# TSAL_inverter_voltage_measurement_TNN_V1.net
KiCad netlist of a schematic drawn in EAGLE
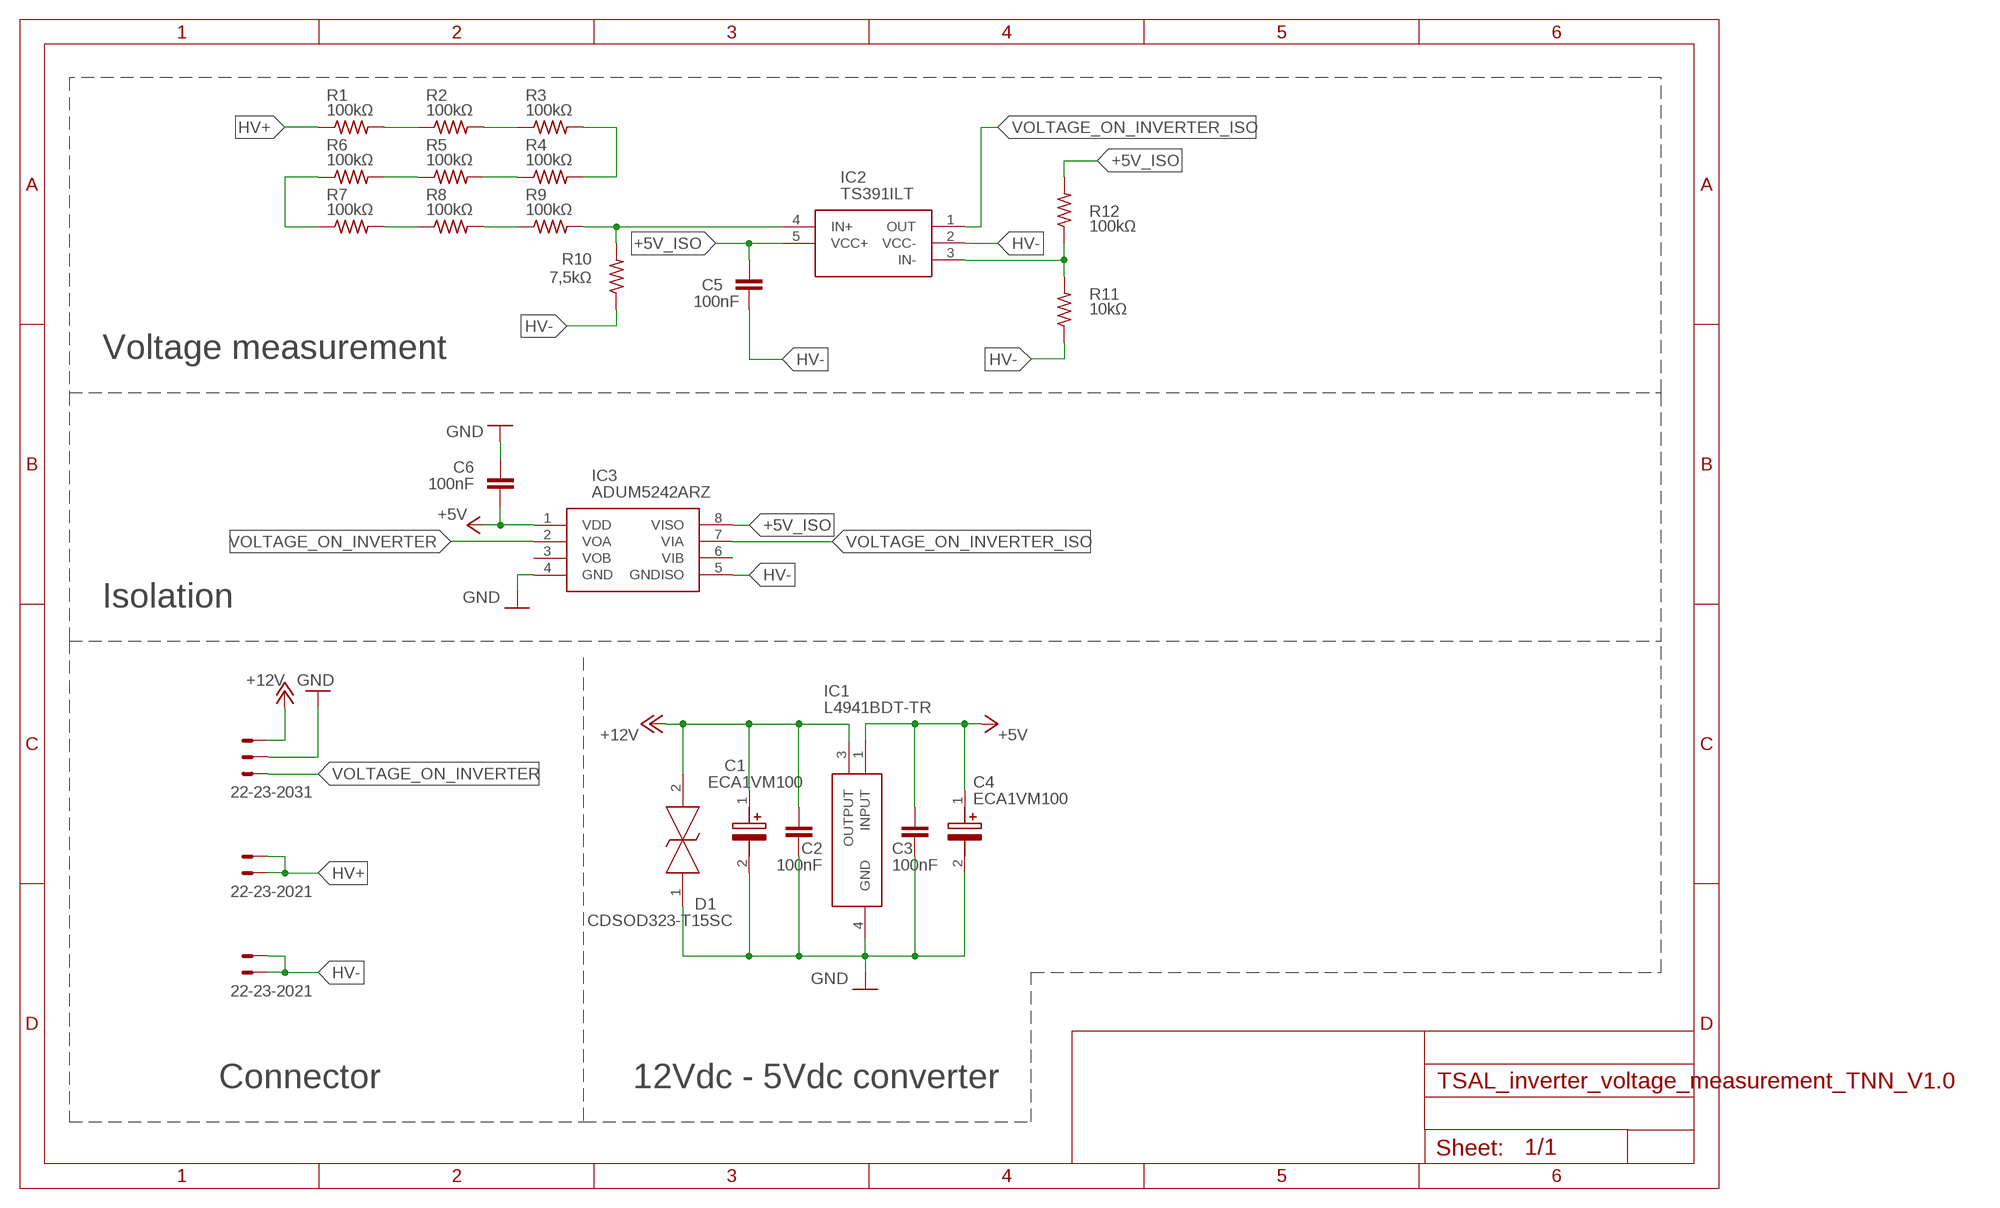
[diagram p0: schematic, sheet 1]

(export (version "E")
  (design (tool "Eeschema 10.0.6"))
  (components
    (comp (ref "C1")
      (value "ECA1VM100")
      (footprint "eagle-import:CAPPRD200W55D525H1200")
      (libsource (lib "eagle-import") (part "ECA1VM100"))
    )
    (comp (ref "C2")
      (value "100nF")
      (footprint "eagle-import:C0603")
      (libsource (lib "eagle-import") (part "C-EUC0603"))
    )
    (comp (ref "C3")
      (value "100nF")
      (footprint "eagle-import:C0603")
      (libsource (lib "eagle-import") (part "C-EUC0603"))
    )
    (comp (ref "C4")
      (value "ECA1VM100")
      (footprint "eagle-import:CAPPRD200W55D525H1200")
      (libsource (lib "eagle-import") (part "ECA1VM100"))
    )
    (comp (ref "C5")
      (value "100nF")
      (footprint "eagle-import:C0603")
      (libsource (lib "eagle-import") (part "C-EUC0603"))
    )
    (comp (ref "C6")
      (value "100nF")
      (footprint "eagle-import:C0603")
      (libsource (lib "eagle-import") (part "C-EUC0603"))
    )
    (comp (ref "D1")
      (value "CDSOD323-T15SC")
      (footprint "eagle-import:SOD-323")
      (fields (field (name "MOUSER_PART_NUMBER") "652-CDSOD323-T15SC"))
      (libsource (lib "eagle-import") (part "CDSOD323-T15SC"))
    )
    (comp (ref "HV+")
      (value "22-23-2021")
      (footprint "eagle-import:22-23-2021")
      (fields (field (name "MF") "MOLEX"))
      (libsource (lib "eagle-import") (part "22-23-2021"))
    )
    (comp (ref "HV-")
      (value "22-23-2021")
      (footprint "eagle-import:22-23-2021")
      (fields (field (name "MF") "MOLEX"))
      (libsource (lib "eagle-import") (part "22-23-2021"))
    )
    (comp (ref "IC1")
      (value "L4941BDT-TR")
      (footprint "eagle-import:TO228P972X240-3N")
      (fields (field (name "MOUSER_PART_NUMBER") "511-L4941BDT-TR"))
      (libsource (lib "eagle-import") (part "L4941BDT-TR"))
    )
    (comp (ref "IC2")
      (value "TS391ILT")
      (footprint "eagle-import:SOT95P280X145-5N")
      (fields (field (name "MOUSER_PART_NUMBER") "511-TS391IL"))
      (libsource (lib "eagle-import") (part "TS391ILT"))
    )
    (comp (ref "IC3")
      (value "ADUM5242ARZ")
      (footprint "eagle-import:SOIC127P600X175-8N")
      (fields (field (name "MOUSER_PART_NUMBER") "584-ADUM5242ARZ"))
      (libsource (lib "eagle-import") (part "ADUM5242ARZ"))
    )
    (comp (ref "LOW_VOLTAGE")
      (value "22-23-2031")
      (footprint "eagle-import:22-23-2031")
      (fields (field (name "MF") "MOLEX"))
      (libsource (lib "eagle-import") (part "22-23-2031"))
    )
    (comp (ref "R1")
      (value "100kΩ")
      (footprint "eagle-import:R0603")
      (libsource (lib "eagle-import") (part "R-US_R0603"))
    )
    (comp (ref "R2")
      (value "100kΩ")
      (footprint "eagle-import:R0603")
      (libsource (lib "eagle-import") (part "R-US_R0603"))
    )
    (comp (ref "R3")
      (value "100kΩ")
      (footprint "eagle-import:R0603")
      (libsource (lib "eagle-import") (part "R-US_R0603"))
    )
    (comp (ref "R4")
      (value "100kΩ")
      (footprint "eagle-import:R0603")
      (libsource (lib "eagle-import") (part "R-US_R0603"))
    )
    (comp (ref "R5")
      (value "100kΩ")
      (footprint "eagle-import:R0603")
      (libsource (lib "eagle-import") (part "R-US_R0603"))
    )
    (comp (ref "R6")
      (value "100kΩ")
      (footprint "eagle-import:R0603")
      (libsource (lib "eagle-import") (part "R-US_R0603"))
    )
    (comp (ref "R7")
      (value "100kΩ")
      (footprint "eagle-import:R0603")
      (libsource (lib "eagle-import") (part "R-US_R0603"))
    )
    (comp (ref "R8")
      (value "100kΩ")
      (footprint "eagle-import:R0603")
      (libsource (lib "eagle-import") (part "R-US_R0603"))
    )
    (comp (ref "R9")
      (value "100kΩ")
      (footprint "eagle-import:R0603")
      (libsource (lib "eagle-import") (part "R-US_R0603"))
    )
    (comp (ref "R10")
      (value "7,5kΩ")
      (footprint "eagle-import:R0603")
      (libsource (lib "eagle-import") (part "R-US_R0603"))
    )
    (comp (ref "R11")
      (value "10kΩ")
      (footprint "eagle-import:R0603")
      (libsource (lib "eagle-import") (part "R-US_R0603"))
    )
    (comp (ref "R12")
      (value "100kΩ")
      (footprint "eagle-import:R0603")
      (libsource (lib "eagle-import") (part "R-US_R0603"))
    )
  )
  (nets
    (net (code "1") (name "+5V") (class "Default")
      (node (ref "C3") (pin "2") (pinfunction "2_2") (pintype "passive"))
      (node (ref "C4") (pin "1") (pinfunction "+_1") (pintype "bidirectional"))
      (node (ref "C6") (pin "1") (pinfunction "1_1") (pintype "passive"))
      (node (ref "IC1") (pin "1") (pinfunction "INPUT_1") (pintype "output"))
      (node (ref "IC3") (pin "1") (pinfunction "VDD_1") (pintype "bidirectional"))
    )
    (net (code "2") (name "+5V_ISO") (class "Default")
      (node (ref "C5") (pin "2") (pinfunction "2_2") (pintype "passive"))
      (node (ref "IC2") (pin "5") (pinfunction "VCC+_5") (pintype "bidirectional"))
      (node (ref "IC3") (pin "8") (pinfunction "VISO_8") (pintype "bidirectional"))
      (node (ref "R12") (pin "2") (pinfunction "2_2") (pintype "passive"))
    )
    (net (code "3") (name "+12V") (class "Default")
      (node (ref "C1") (pin "1") (pinfunction "+_1") (pintype "bidirectional"))
      (node (ref "C2") (pin "2") (pinfunction "2_2") (pintype "passive"))
      (node (ref "D1") (pin "2") (pinfunction "2_2") (pintype "bidirectional"))
      (node (ref "IC1") (pin "3") (pinfunction "OUTPUT_3") (pintype "power_in"))
      (node (ref "LOW_VOLTAGE") (pin "3") (pinfunction "S_3") (pintype "passive"))
    )
    (net (code "4") (name "GND") (class "Default")
      (node (ref "C1") (pin "2") (pinfunction "-_2") (pintype "bidirectional"))
      (node (ref "C2") (pin "1") (pinfunction "1_1") (pintype "passive"))
      (node (ref "C3") (pin "1") (pinfunction "1_1") (pintype "passive"))
      (node (ref "C4") (pin "2") (pinfunction "-_2") (pintype "bidirectional"))
      (node (ref "C6") (pin "2") (pinfunction "2_2") (pintype "passive"))
      (node (ref "D1") (pin "1") (pinfunction "1_1") (pintype "bidirectional"))
      (node (ref "IC1") (pin "4") (pinfunction "GND_4") (pintype "input"))
      (node (ref "IC3") (pin "4") (pinfunction "GND_4") (pintype "bidirectional"))
      (node (ref "LOW_VOLTAGE") (pin "2") (pinfunction "S_2") (pintype "passive"))
    )
    (net (code "5") (name "HV+") (class "Default")
      (node (ref "HV+") (pin "1") (pinfunction "S_1") (pintype "passive"))
      (node (ref "HV+") (pin "2") (pinfunction "S_2") (pintype "passive"))
      (node (ref "R1") (pin "1") (pinfunction "1_1") (pintype "passive"))
    )
    (net (code "6") (name "HV-") (class "Default")
      (node (ref "C5") (pin "1") (pinfunction "1_1") (pintype "passive"))
      (node (ref "HV-") (pin "1") (pinfunction "S_1") (pintype "passive"))
      (node (ref "HV-") (pin "2") (pinfunction "S_2") (pintype "passive"))
      (node (ref "IC2") (pin "2") (pinfunction "VCC-_2") (pintype "bidirectional"))
      (node (ref "IC3") (pin "5") (pinfunction "GNDISO_5") (pintype "bidirectional"))
      (node (ref "R10") (pin "1") (pinfunction "1_1") (pintype "passive"))
      (node (ref "R11") (pin "1") (pinfunction "1_1") (pintype "passive"))
    )
    (net (code "7") (name "Net-(IC2-IN+)") (class "Default")
      (node (ref "IC2") (pin "4") (pinfunction "IN+_4") (pintype "bidirectional"))
      (node (ref "R10") (pin "2") (pinfunction "2_2") (pintype "passive"))
      (node (ref "R9") (pin "2") (pinfunction "2_2") (pintype "passive"))
    )
    (net (code "8") (name "Net-(IC2-IN-)") (class "Default")
      (node (ref "IC2") (pin "3") (pinfunction "IN-_3") (pintype "bidirectional"))
      (node (ref "R11") (pin "2") (pinfunction "2_2") (pintype "passive"))
      (node (ref "R12") (pin "1") (pinfunction "1_1") (pintype "passive"))
    )
    (net (code "9") (name "Net-(R1-Pad2)") (class "Default")
      (node (ref "R1") (pin "2") (pinfunction "2_2") (pintype "passive"))
      (node (ref "R2") (pin "1") (pinfunction "1_1") (pintype "passive"))
    )
    (net (code "10") (name "Net-(R2-Pad2)") (class "Default")
      (node (ref "R2") (pin "2") (pinfunction "2_2") (pintype "passive"))
      (node (ref "R3") (pin "1") (pinfunction "1_1") (pintype "passive"))
    )
    (net (code "11") (name "Net-(R3-Pad2)") (class "Default")
      (node (ref "R3") (pin "2") (pinfunction "2_2") (pintype "passive"))
      (node (ref "R4") (pin "2") (pinfunction "2_2") (pintype "passive"))
    )
    (net (code "12") (name "Net-(R4-Pad1)") (class "Default")
      (node (ref "R4") (pin "1") (pinfunction "1_1") (pintype "passive"))
      (node (ref "R5") (pin "2") (pinfunction "2_2") (pintype "passive"))
    )
    (net (code "13") (name "Net-(R5-Pad1)") (class "Default")
      (node (ref "R5") (pin "1") (pinfunction "1_1") (pintype "passive"))
      (node (ref "R6") (pin "2") (pinfunction "2_2") (pintype "passive"))
    )
    (net (code "14") (name "Net-(R6-Pad1)") (class "Default")
      (node (ref "R6") (pin "1") (pinfunction "1_1") (pintype "passive"))
      (node (ref "R7") (pin "1") (pinfunction "1_1") (pintype "passive"))
    )
    (net (code "15") (name "Net-(R7-Pad2)") (class "Default")
      (node (ref "R7") (pin "2") (pinfunction "2_2") (pintype "passive"))
      (node (ref "R8") (pin "1") (pinfunction "1_1") (pintype "passive"))
    )
    (net (code "16") (name "Net-(R8-Pad2)") (class "Default")
      (node (ref "R8") (pin "2") (pinfunction "2_2") (pintype "passive"))
      (node (ref "R9") (pin "1") (pinfunction "1_1") (pintype "passive"))
    )
    (net (code "17") (name "VOLTAGE_ON_INVERTER") (class "Default")
      (node (ref "IC3") (pin "2") (pinfunction "VOA_2") (pintype "bidirectional"))
      (node (ref "LOW_VOLTAGE") (pin "1") (pinfunction "S_1") (pintype "passive"))
    )
    (net (code "18") (name "VOLTAGE_ON_INVERTER_ISO") (class "Default")
      (node (ref "IC2") (pin "1") (pinfunction "OUT_1") (pintype "bidirectional"))
      (node (ref "IC3") (pin "7") (pinfunction "VIA_7") (pintype "bidirectional"))
    )
    (net (code "19") (name "unconnected-(IC3-VIB-Pad6)") (class "Default")
      (node (ref "IC3") (pin "6") (pinfunction "VIB_6") (pintype "bidirectional"))
    )
    (net (code "20") (name "unconnected-(IC3-VOB-Pad3)") (class "Default")
      (node (ref "IC3") (pin "3") (pinfunction "VOB_3") (pintype "bidirectional"))
    )
  )
)
